# MCU.net
KiCad netlist of a schematic drawn in Altium Designer
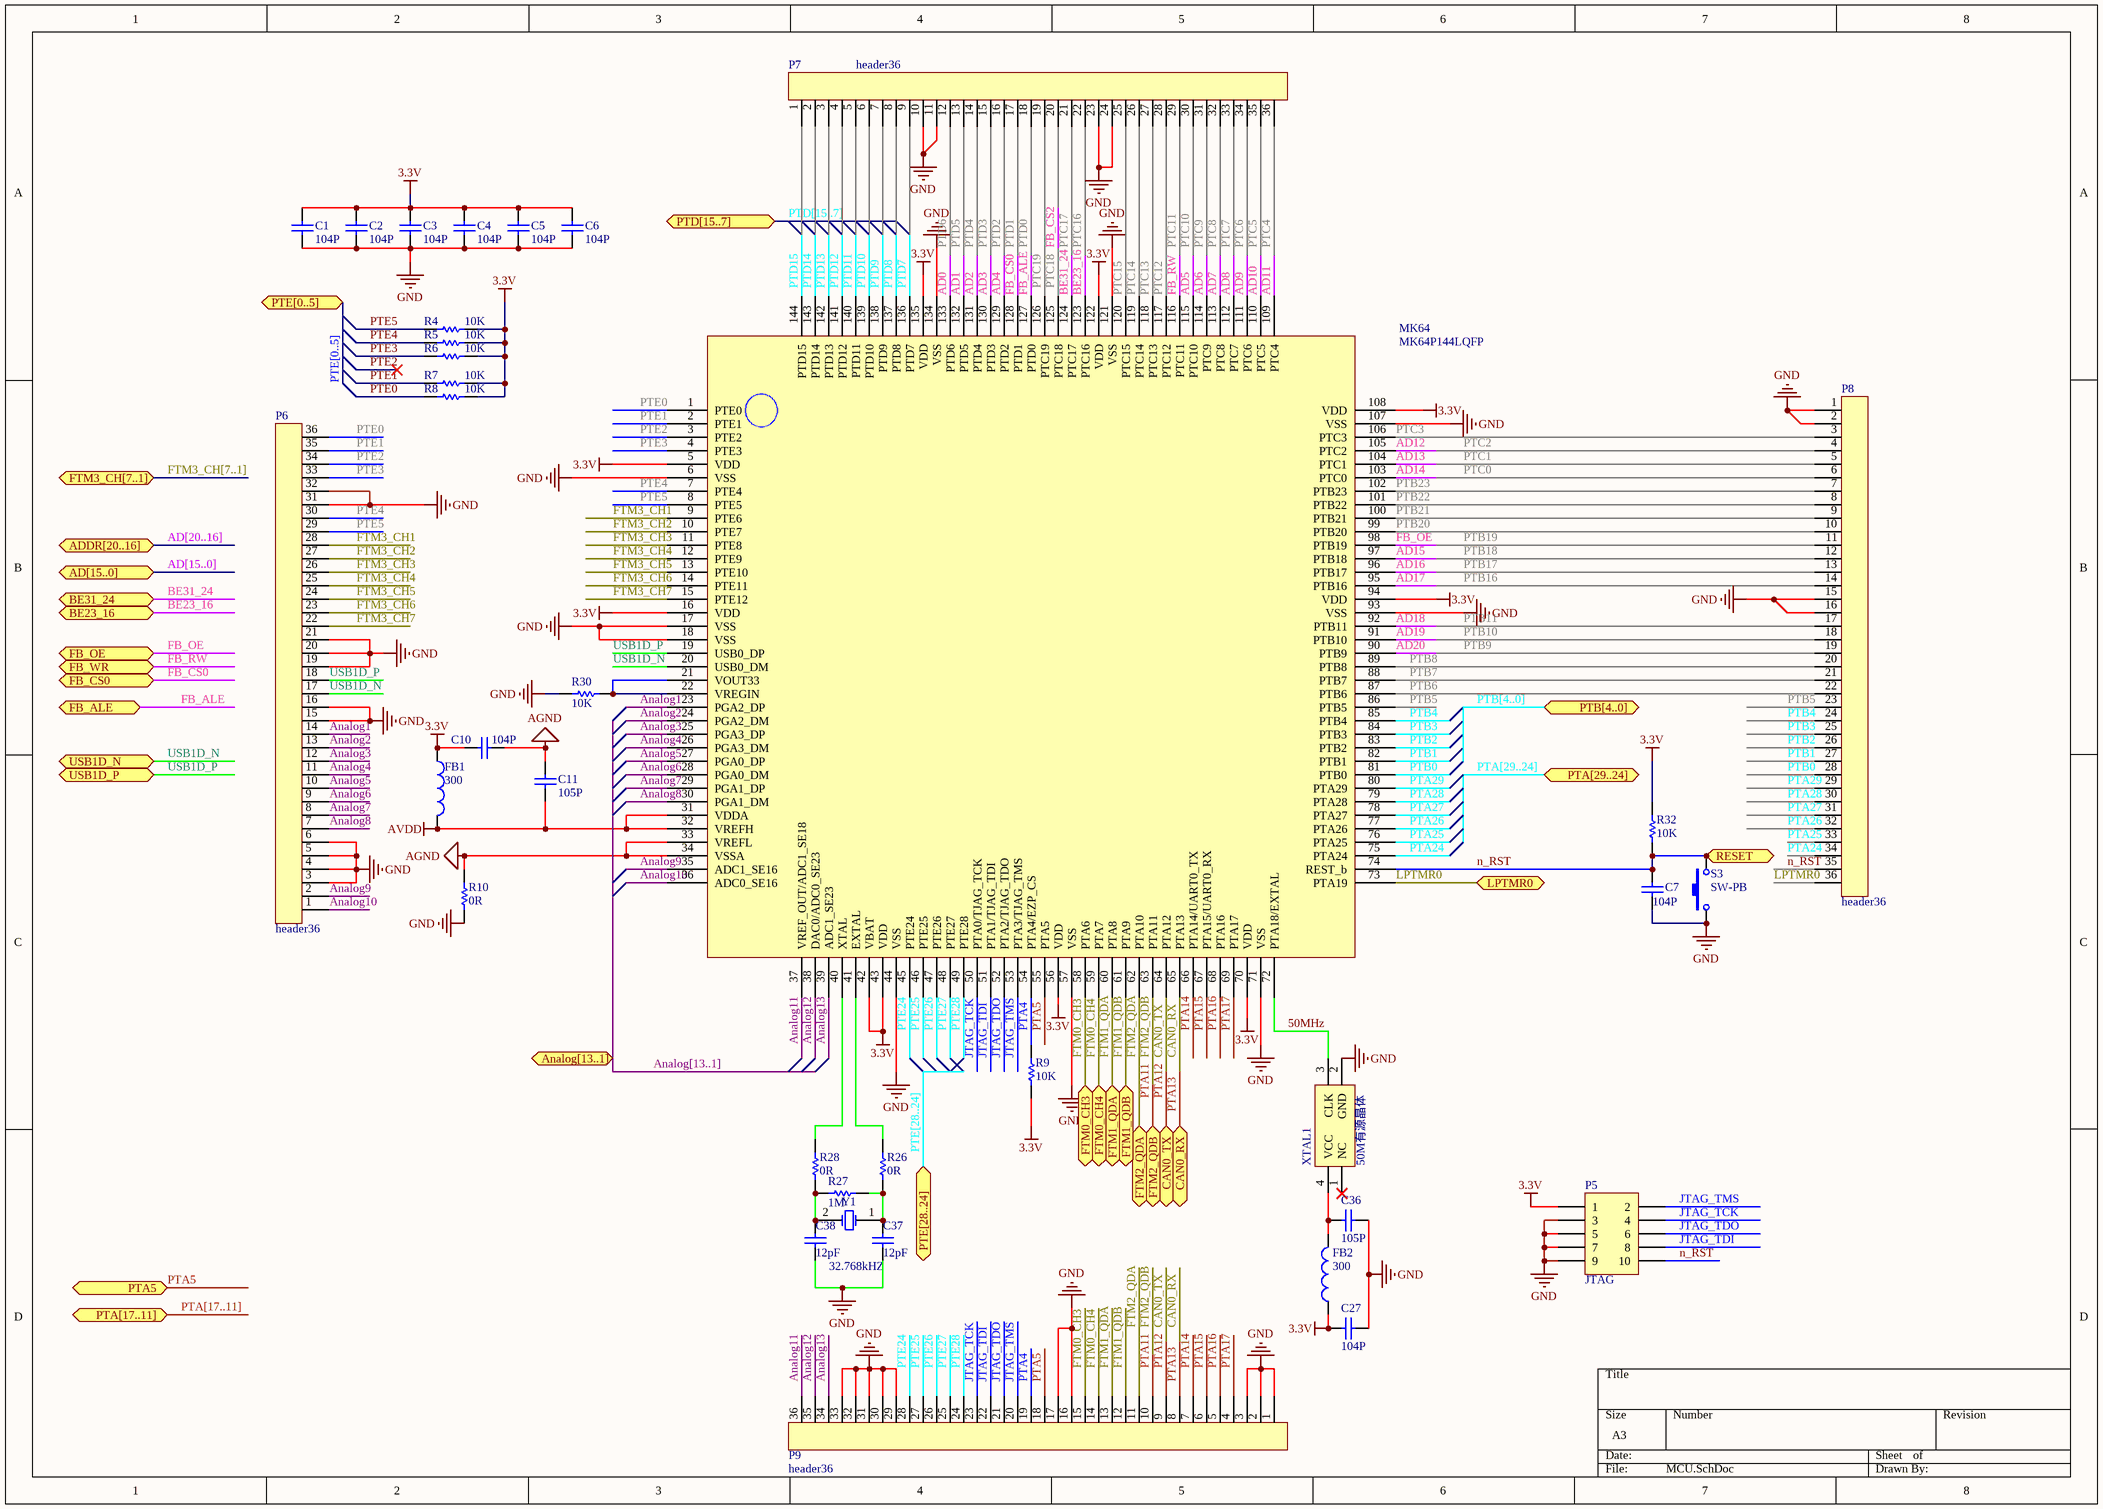
[diagram p0: MCU.SchDoc]

(export (version "E")
  (design (tool "Eeschema 10.0.6"))
  (components
    (comp (ref "C1")
      (value "104P")
      (footprint "1608[0603]")
      (description "贴片电容")
      (fields (field (name "Comment") "Cap") (field (name "PUBLISHER") "Altium Limited"))
      (libsource (lib "Sparks") (part "Cap"))
    )
    (comp (ref "C2")
      (value "104P")
      (footprint "1608[0603]")
      (description "贴片电容")
      (fields (field (name "Comment") "Cap") (field (name "PUBLISHER") "Altium Limited"))
      (libsource (lib "Sparks") (part "Cap"))
    )
    (comp (ref "C3")
      (value "104P")
      (footprint "1608[0603]")
      (description "贴片电容")
      (fields (field (name "Comment") "Cap") (field (name "PUBLISHER") "Altium Limited"))
      (libsource (lib "Sparks") (part "Cap"))
    )
    (comp (ref "C4")
      (value "104P")
      (footprint "1608[0603]")
      (description "贴片电容")
      (fields (field (name "Comment") "Cap") (field (name "PUBLISHER") "Altium Limited"))
      (libsource (lib "Sparks") (part "Cap"))
    )
    (comp (ref "C5")
      (value "104P")
      (footprint "1608[0603]")
      (description "贴片电容")
      (fields (field (name "Comment") "Cap") (field (name "PUBLISHER") "Altium Limited"))
      (libsource (lib "Sparks") (part "Cap"))
    )
    (comp (ref "C6")
      (value "104P")
      (footprint "1608[0603]")
      (description "贴片电容")
      (fields (field (name "Comment") "Cap") (field (name "PUBLISHER") "Altium Limited"))
      (libsource (lib "Sparks") (part "Cap"))
    )
    (comp (ref "C7")
      (value "104P")
      (footprint "1608[0603]")
      (description "贴片电容")
      (fields (field (name "Comment") "Cap") (field (name "PUBLISHER") "Altium Limited"))
      (libsource (lib "Sparks") (part "Cap"))
    )
    (comp (ref "C10")
      (value "104P")
      (footprint "1608[0603]")
      (description "贴片电容")
      (fields (field (name "Comment") "Cap") (field (name "PUBLISHER") "Altium Limited"))
      (libsource (lib "Sparks") (part "Cap"))
    )
    (comp (ref "C11")
      (value "105P")
      (footprint "1608[0603]")
      (description "贴片电容")
      (fields (field (name "Comment") "Cap") (field (name "PUBLISHER") "Altium Limited"))
      (libsource (lib "Sparks") (part "Cap"))
    )
    (comp (ref "C27")
      (value "104P")
      (footprint "1608[0603]")
      (description "贴片电容")
      (fields (field (name "Comment") "Cap") (field (name "PUBLISHER") "Altium Limited"))
      (libsource (lib "Sparks") (part "Cap"))
    )
    (comp (ref "C36")
      (value "105P")
      (footprint "1608[0603]")
      (description "贴片电容")
      (fields (field (name "Comment") "Cap") (field (name "PUBLISHER") "Altium Limited"))
      (libsource (lib "Sparks") (part "Cap"))
    )
    (comp (ref "C37")
      (value "12pF")
      (footprint "1608[0603]")
      (description "贴片电容")
      (fields (field (name "Comment") "Cap") (field (name "PUBLISHER") "Altium Limited"))
      (libsource (lib "Sparks") (part "Cap"))
    )
    (comp (ref "C38")
      (value "12pF")
      (footprint "1608[0603]")
      (description "贴片电容")
      (fields (field (name "Comment") "Cap") (field (name "PUBLISHER") "Altium Limited"))
      (libsource (lib "Sparks") (part "Cap"))
    )
    (comp (ref "FB1")
      (value "300")
      (footprint "1608[0603]")
      (description "Inductor")
      (fields (field (name "PUBLISHER") "Altium Limited"))
      (libsource (lib "Miscellaneous Devices") (part "Inductor"))
    )
    (comp (ref "FB2")
      (value "300")
      (footprint "1608[0603]")
      (description "Inductor")
      (fields (field (name "PUBLISHER") "Altium Limited"))
      (libsource (lib "Miscellaneous Devices") (part "Inductor"))
    )
    (comp (ref "MK64")
      (value "MK64P144LQFP")
      (footprint "LQFP-144")
      (libsource (lib "2号库") (part "MK64P144LQFP"))
    )
    (comp (ref "P5")
      (value "JTAG")
      (footprint "MHDR2X5")
      (description "Header, 5-Pin, Dual row")
      (fields (field (name "PUBLISHER") "Altium Limited"))
      (libsource (lib "Sparks") (part "Header 5X2"))
    )
    (comp (ref "P6") (value "header36") (footprint "FFC/SM0.5-2H36") (libsource (lib "") (part "header36_1")))
    (comp (ref "P7") (value "header36") (footprint "FFC/SM0.5-2H36") (libsource (lib "") (part "header36_2")))
    (comp (ref "P8") (value "header36") (footprint "FFC/SM0.5-2H36") (libsource (lib "") (part "header36_3")))
    (comp (ref "P9")
      (value "header36")
      (footprint "FFC/SM0.5-2H36")
      (libsource (lib "2号库") (part "header36"))
    )
    (comp (ref "R4")
      (value "10K")
      (footprint "1608[0603]")
      (description "贴片电阻")
      (fields (field (name "Comment") "Res") (field (name "PUBLISHER") "Altium Limited"))
      (libsource (lib "Sparks") (part "Res"))
    )
    (comp (ref "R5")
      (value "10K")
      (footprint "1608[0603]")
      (description "贴片电阻")
      (fields (field (name "Comment") "Res") (field (name "PUBLISHER") "Altium Limited"))
      (libsource (lib "Sparks") (part "Res"))
    )
    (comp (ref "R6")
      (value "10K")
      (footprint "1608[0603]")
      (description "贴片电阻")
      (fields (field (name "Comment") "Res") (field (name "PUBLISHER") "Altium Limited"))
      (libsource (lib "Sparks") (part "Res"))
    )
    (comp (ref "R7")
      (value "10K")
      (footprint "1608[0603]")
      (description "贴片电阻")
      (fields (field (name "Comment") "Res") (field (name "PUBLISHER") "Altium Limited"))
      (libsource (lib "Sparks") (part "Res"))
    )
    (comp (ref "R8")
      (value "10K")
      (footprint "1608[0603]")
      (description "贴片电阻")
      (fields (field (name "Comment") "Res") (field (name "PUBLISHER") "Altium Limited"))
      (libsource (lib "Sparks") (part "Res"))
    )
    (comp (ref "R9")
      (value "10K")
      (footprint "1608[0603]")
      (description "贴片电阻")
      (fields (field (name "Comment") "Res") (field (name "PUBLISHER") "Altium Limited"))
      (libsource (lib "Sparks") (part "Res"))
    )
    (comp (ref "R10")
      (value "0R")
      (footprint "1608[0603]")
      (description "贴片电阻")
      (fields (field (name "Comment") "Res") (field (name "PUBLISHER") "Altium Limited"))
      (libsource (lib "Sparks") (part "Res"))
    )
    (comp (ref "R26")
      (value "0R")
      (footprint "1608[0603]")
      (description "贴片电阻")
      (fields (field (name "Comment") "Res") (field (name "PUBLISHER") "Altium Limited"))
      (libsource (lib "Sparks") (part "Res"))
    )
    (comp (ref "R27")
      (value "1M")
      (footprint "1608[0603]")
      (description "贴片电阻")
      (fields (field (name "Comment") "Res") (field (name "PUBLISHER") "Altium Limited"))
      (libsource (lib "Sparks") (part "Res"))
    )
    (comp (ref "R28")
      (value "0R")
      (footprint "1608[0603]")
      (description "贴片电阻")
      (fields (field (name "Comment") "Res") (field (name "PUBLISHER") "Altium Limited"))
      (libsource (lib "Sparks") (part "Res"))
    )
    (comp (ref "R30")
      (value "10K")
      (footprint "1608[0603]")
      (description "贴片电阻")
      (fields (field (name "Comment") "Res") (field (name "PUBLISHER") "Altium Limited"))
      (libsource (lib "Sparks") (part "Res"))
    )
    (comp (ref "R32")
      (value "10K")
      (footprint "1608[0603]")
      (description "贴片电阻")
      (fields (field (name "Comment") "Res") (field (name "PUBLISHER") "Altium Limited"))
      (libsource (lib "Sparks") (part "Res"))
    )
    (comp (ref "S3")
      (value "SW-PB")
      (footprint "key 3*4*2")
      (description "Switch")
      (libsource (lib "K60-V4.0") (part "SW-PB"))
    )
    (comp (ref "XTAL1") (value "50M有源晶体") (footprint "XTAL7_3225") (libsource (lib "Sparks") (part "有源晶体")))
    (comp (ref "Y1")
      (value "32.768kHZ")
      (footprint "3215")
      (description "晶体振荡器")
      (fields (field (name "PUBLISHER") "Altium Limited"))
      (libsource (lib "Sparks") (part "XTAL"))
    )
  )
  (nets
    (net (code "1") (name "/50MHz") (class "Default")
      (node (ref "MK64") (pin "72") (pinfunction "PTA18/EXTAL_72") (pintype "passive"))
      (node (ref "XTAL1") (pin "3") (pinfunction "CLK_3") (pintype "passive"))
    )
    (net (code "2") (name "/AD0") (class "Default")
      (node (ref "MK64") (pin "133") (pinfunction "PTD6_133") (pintype "passive"))
      (node (ref "P7") (pin "12") (pinfunction "12_12") (pintype "passive"))
    )
    (net (code "3") (name "/AD1") (class "Default")
      (node (ref "MK64") (pin "132") (pinfunction "PTD5_132") (pintype "passive"))
      (node (ref "P7") (pin "13") (pinfunction "13_13") (pintype "passive"))
    )
    (net (code "4") (name "/AD2") (class "Default")
      (node (ref "MK64") (pin "131") (pinfunction "PTD4_131") (pintype "passive"))
      (node (ref "P7") (pin "14") (pinfunction "14_14") (pintype "passive"))
    )
    (net (code "5") (name "/AD3") (class "Default")
      (node (ref "MK64") (pin "130") (pinfunction "PTD3_130") (pintype "passive"))
      (node (ref "P7") (pin "15") (pinfunction "15_15") (pintype "passive"))
    )
    (net (code "6") (name "/AD4") (class "Default")
      (node (ref "MK64") (pin "129") (pinfunction "PTD2_129") (pintype "passive"))
      (node (ref "P7") (pin "16") (pinfunction "16_16") (pintype "passive"))
    )
    (net (code "7") (name "/AD5") (class "Default")
      (node (ref "MK64") (pin "115") (pinfunction "PTC10_115") (pintype "passive"))
      (node (ref "P7") (pin "30") (pinfunction "30_30") (pintype "passive"))
    )
    (net (code "8") (name "/AD6") (class "Default")
      (node (ref "MK64") (pin "114") (pinfunction "PTC9_114") (pintype "passive"))
      (node (ref "P7") (pin "31") (pinfunction "31_31") (pintype "passive"))
    )
    (net (code "9") (name "/AD7") (class "Default")
      (node (ref "MK64") (pin "113") (pinfunction "PTC8_113") (pintype "passive"))
      (node (ref "P7") (pin "32") (pinfunction "32_32") (pintype "passive"))
    )
    (net (code "10") (name "/AD8") (class "Default")
      (node (ref "MK64") (pin "112") (pinfunction "PTC7_112") (pintype "passive"))
      (node (ref "P7") (pin "33") (pinfunction "33_33") (pintype "passive"))
    )
    (net (code "11") (name "/AD9") (class "Default")
      (node (ref "MK64") (pin "111") (pinfunction "PTC6_111") (pintype "passive"))
      (node (ref "P7") (pin "34") (pinfunction "34_34") (pintype "passive"))
    )
    (net (code "12") (name "/AD10") (class "Default")
      (node (ref "MK64") (pin "110") (pinfunction "PTC5_110") (pintype "passive"))
      (node (ref "P7") (pin "35") (pinfunction "35_35") (pintype "passive"))
    )
    (net (code "13") (name "/AD11") (class "Default")
      (node (ref "MK64") (pin "109") (pinfunction "PTC4_109") (pintype "passive"))
      (node (ref "P7") (pin "36") (pinfunction "36_36") (pintype "passive"))
    )
    (net (code "14") (name "/AD12") (class "Default")
      (node (ref "MK64") (pin "105") (pinfunction "PTC2_105") (pintype "passive"))
      (node (ref "P8") (pin "4") (pinfunction "4_4") (pintype "passive"))
    )
    (net (code "15") (name "/AD13") (class "Default")
      (node (ref "MK64") (pin "104") (pinfunction "PTC1_104") (pintype "passive"))
      (node (ref "P8") (pin "5") (pinfunction "5_5") (pintype "passive"))
    )
    (net (code "16") (name "/AD14") (class "Default")
      (node (ref "MK64") (pin "103") (pinfunction "PTC0_103") (pintype "passive"))
      (node (ref "P8") (pin "6") (pinfunction "6_6") (pintype "passive"))
    )
    (net (code "17") (name "/AD15") (class "Default")
      (node (ref "MK64") (pin "97") (pinfunction "PTB18_97") (pintype "passive"))
      (node (ref "P8") (pin "12") (pinfunction "12_12") (pintype "passive"))
    )
    (net (code "18") (name "/AD16") (class "Default")
      (node (ref "MK64") (pin "96") (pinfunction "PTB17_96") (pintype "passive"))
      (node (ref "P8") (pin "13") (pinfunction "13_13") (pintype "passive"))
    )
    (net (code "19") (name "/AD17") (class "Default")
      (node (ref "MK64") (pin "95") (pinfunction "PTB16_95") (pintype "passive"))
      (node (ref "P8") (pin "14") (pinfunction "14_14") (pintype "passive"))
    )
    (net (code "20") (name "/AD18") (class "Default")
      (node (ref "MK64") (pin "92") (pinfunction "PTB11_92") (pintype "passive"))
      (node (ref "P8") (pin "17") (pinfunction "17_17") (pintype "passive"))
    )
    (net (code "21") (name "/AD19") (class "Default")
      (node (ref "MK64") (pin "91") (pinfunction "PTB10_91") (pintype "passive"))
      (node (ref "P8") (pin "18") (pinfunction "18_18") (pintype "passive"))
    )
    (net (code "22") (name "/AD20") (class "Default")
      (node (ref "MK64") (pin "90") (pinfunction "PTB9_90") (pintype "passive"))
      (node (ref "P8") (pin "19") (pinfunction "19_19") (pintype "passive"))
    )
    (net (code "25") (name "/Analog1") (class "Default")
      (node (ref "MK64") (pin "23") (pinfunction "PGA2_DP_23") (pintype "passive"))
      (node (ref "P6") (pin "14") (pinfunction "14_14") (pintype "passive"))
    )
    (net (code "26") (name "/Analog2") (class "Default")
      (node (ref "MK64") (pin "24") (pinfunction "PGA2_DM_24") (pintype "passive"))
      (node (ref "P6") (pin "13") (pinfunction "13_13") (pintype "passive"))
    )
    (net (code "27") (name "/Analog3") (class "Default")
      (node (ref "MK64") (pin "25") (pinfunction "PGA3_DP_25") (pintype "passive"))
      (node (ref "P6") (pin "12") (pinfunction "12_12") (pintype "passive"))
    )
    (net (code "28") (name "/Analog4") (class "Default")
      (node (ref "MK64") (pin "26") (pinfunction "PGA3_DM_26") (pintype "passive"))
      (node (ref "P6") (pin "11") (pinfunction "11_11") (pintype "passive"))
    )
    (net (code "29") (name "/Analog5") (class "Default")
      (node (ref "MK64") (pin "27") (pinfunction "PGA0_DP_27") (pintype "passive"))
      (node (ref "P6") (pin "10") (pinfunction "10_10") (pintype "passive"))
    )
    (net (code "30") (name "/Analog6") (class "Default")
      (node (ref "MK64") (pin "28") (pinfunction "PGA0_DM_28") (pintype "passive"))
      (node (ref "P6") (pin "9") (pinfunction "9_9") (pintype "passive"))
    )
    (net (code "31") (name "/Analog7") (class "Default")
      (node (ref "MK64") (pin "29") (pinfunction "PGA1_DP_29") (pintype "passive"))
      (node (ref "P6") (pin "8") (pinfunction "8_8") (pintype "passive"))
    )
    (net (code "32") (name "/Analog8") (class "Default")
      (node (ref "MK64") (pin "30") (pinfunction "PGA1_DM_30") (pintype "passive"))
      (node (ref "P6") (pin "7") (pinfunction "7_7") (pintype "passive"))
    )
    (net (code "33") (name "/Analog9") (class "Default")
      (node (ref "MK64") (pin "35") (pinfunction "ADC1_SE16_35") (pintype "passive"))
      (node (ref "P6") (pin "2") (pinfunction "2_2") (pintype "passive"))
    )
    (net (code "34") (name "/Analog10") (class "Default")
      (node (ref "MK64") (pin "36") (pinfunction "ADC0_SE16_36") (pintype "passive"))
      (node (ref "P6") (pin "1") (pinfunction "1_1") (pintype "passive"))
    )
    (net (code "35") (name "/Analog11") (class "Default")
      (node (ref "MK64") (pin "37") (pinfunction "VREF_OUT/ADC1_SE18_37") (pintype "passive"))
      (node (ref "P9") (pin "36") (pinfunction "36_36") (pintype "passive"))
    )
    (net (code "36") (name "/Analog12") (class "Default")
      (node (ref "MK64") (pin "38") (pinfunction "DAC0/ADC0_SE23_38") (pintype "passive"))
      (node (ref "P9") (pin "35") (pinfunction "35_35") (pintype "passive"))
    )
    (net (code "37") (name "/Analog13") (class "Default")
      (node (ref "MK64") (pin "39") (pinfunction "ADC1_SE23_39") (pintype "passive"))
      (node (ref "P9") (pin "34") (pinfunction "34_34") (pintype "passive"))
    )
    (net (code "39") (name "/BE23_16") (class "Default")
      (node (ref "MK64") (pin "123") (pinfunction "PTC16_123") (pintype "passive"))
      (node (ref "P7") (pin "22") (pinfunction "22_22") (pintype "passive"))
    )
    (net (code "40") (name "/BE31_24") (class "Default")
      (node (ref "MK64") (pin "124") (pinfunction "PTC17_124") (pintype "passive"))
      (node (ref "P7") (pin "21") (pinfunction "21_21") (pintype "passive"))
    )
    (net (code "41") (name "/FB_ALE") (class "Default")
      (node (ref "MK64") (pin "127") (pinfunction "PTD0_127") (pintype "passive"))
      (node (ref "P7") (pin "18") (pinfunction "18_18") (pintype "passive"))
    )
    (net (code "42") (name "/FB_CS0") (class "Default")
      (node (ref "MK64") (pin "128") (pinfunction "PTD1_128") (pintype "passive"))
      (node (ref "P7") (pin "17") (pinfunction "17_17") (pintype "passive"))
    )
    (net (code "43") (name "/FB_CS2") (class "Default")
      (node (ref "MK64") (pin "125") (pinfunction "PTC18_125") (pintype "passive"))
      (node (ref "P7") (pin "20") (pinfunction "20_20") (pintype "passive"))
    )
    (net (code "44") (name "/FB_OE") (class "Default")
      (node (ref "MK64") (pin "98") (pinfunction "PTB19_98") (pintype "passive"))
      (node (ref "P8") (pin "11") (pinfunction "11_11") (pintype "passive"))
    )
    (net (code "45") (name "/FB_RW") (class "Default")
      (node (ref "MK64") (pin "116") (pinfunction "PTC11_116") (pintype "passive"))
      (node (ref "P7") (pin "29") (pinfunction "29_29") (pintype "passive"))
    )
    (net (code "46") (name "/FTM0_CH3") (class "Default")
      (node (ref "MK64") (pin "58") (pinfunction "PTA6_58") (pintype "passive"))
      (node (ref "P9") (pin "15") (pinfunction "15_15") (pintype "passive"))
    )
    (net (code "47") (name "/FTM0_CH4") (class "Default")
      (node (ref "MK64") (pin "59") (pinfunction "PTA7_59") (pintype "passive"))
      (node (ref "P9") (pin "14") (pinfunction "14_14") (pintype "passive"))
    )
    (net (code "48") (name "/FTM1_QDA") (class "Default")
      (node (ref "MK64") (pin "60") (pinfunction "PTA8_60") (pintype "passive"))
      (node (ref "P9") (pin "13") (pinfunction "13_13") (pintype "passive"))
    )
    (net (code "49") (name "/FTM1_QDB") (class "Default")
      (node (ref "MK64") (pin "61") (pinfunction "PTA9_61") (pintype "passive"))
      (node (ref "P9") (pin "12") (pinfunction "12_12") (pintype "passive"))
    )
    (net (code "50") (name "/FTM2_QDA") (class "Default")
      (node (ref "MK64") (pin "62") (pinfunction "PTA10_62") (pintype "passive"))
      (node (ref "P9") (pin "11") (pinfunction "11_11") (pintype "passive"))
    )
    (net (code "51") (name "/FTM3_CH1") (class "Default")
      (node (ref "MK64") (pin "9") (pinfunction "PTE6_9") (pintype "passive"))
      (node (ref "P6") (pin "28") (pinfunction "28_28") (pintype "passive"))
    )
    (net (code "52") (name "/FTM3_CH2") (class "Default")
      (node (ref "MK64") (pin "10") (pinfunction "PTE7_10") (pintype "passive"))
      (node (ref "P6") (pin "27") (pinfunction "27_27") (pintype "passive"))
    )
    (net (code "53") (name "/FTM3_CH3") (class "Default")
      (node (ref "MK64") (pin "11") (pinfunction "PTE8_11") (pintype "passive"))
      (node (ref "P6") (pin "26") (pinfunction "26_26") (pintype "passive"))
    )
    (net (code "54") (name "/FTM3_CH4") (class "Default")
      (node (ref "MK64") (pin "12") (pinfunction "PTE9_12") (pintype "passive"))
      (node (ref "P6") (pin "25") (pinfunction "25_25") (pintype "passive"))
    )
    (net (code "55") (name "/FTM3_CH5") (class "Default")
      (node (ref "MK64") (pin "13") (pinfunction "PTE10_13") (pintype "passive"))
      (node (ref "P6") (pin "24") (pinfunction "24_24") (pintype "passive"))
    )
    (net (code "56") (name "/FTM3_CH6") (class "Default")
      (node (ref "MK64") (pin "14") (pinfunction "PTE11_14") (pintype "passive"))
      (node (ref "P6") (pin "23") (pinfunction "23_23") (pintype "passive"))
    )
    (net (code "57") (name "/FTM3_CH7") (class "Default")
      (node (ref "MK64") (pin "15") (pinfunction "PTE12_15") (pintype "passive"))
      (node (ref "P6") (pin "22") (pinfunction "22_22") (pintype "passive"))
    )
    (net (code "59") (name "/JTAG_TCK") (class "Default")
      (node (ref "MK64") (pin "50") (pinfunction "PTA0/TJAG_TCK_50") (pintype "passive"))
      (node (ref "P5") (pin "4") (pinfunction "4_4") (pintype "passive"))
      (node (ref "P9") (pin "23") (pinfunction "23_23") (pintype "passive"))
    )
    (net (code "60") (name "/JTAG_TDI") (class "Default")
      (node (ref "MK64") (pin "51") (pinfunction "PTA1/TJAG_TDI_51") (pintype "passive"))
      (node (ref "P5") (pin "8") (pinfunction "8_8") (pintype "passive"))
      (node (ref "P9") (pin "22") (pinfunction "22_22") (pintype "passive"))
    )
    (net (code "61") (name "/JTAG_TDO") (class "Default")
      (node (ref "MK64") (pin "52") (pinfunction "PTA2/TJAG_TDO_52") (pintype "passive"))
      (node (ref "P5") (pin "6") (pinfunction "6_6") (pintype "passive"))
      (node (ref "P9") (pin "21") (pinfunction "21_21") (pintype "passive"))
    )
    (net (code "62") (name "/JTAG_TMS") (class "Default")
      (node (ref "MK64") (pin "53") (pinfunction "PTA3/TJAG_TMS_53") (pintype "passive"))
      (node (ref "P5") (pin "2") (pinfunction "2_2") (pintype "passive"))
      (node (ref "P9") (pin "20") (pinfunction "20_20") (pintype "passive"))
    )
    (net (code "63") (name "/LPTMR0") (class "Default")
      (node (ref "MK64") (pin "73") (pinfunction "PTA19_73") (pintype "passive"))
      (node (ref "P8") (pin "36") (pinfunction "36_36") (pintype "passive"))
    )
    (net (code "64") (name "/PTA4") (class "Default")
      (node (ref "MK64") (pin "54") (pinfunction "PTA4/EZP_CS_54") (pintype "passive"))
      (node (ref "P9") (pin "19") (pinfunction "19_19") (pintype "passive"))
      (node (ref "R9") (pin "2") (pinfunction "2_2") (pintype "passive"))
    )
    (net (code "65") (name "/PTA5") (class "Default")
      (node (ref "MK64") (pin "55") (pinfunction "PTA5_55") (pintype "passive"))
      (node (ref "P9") (pin "18") (pinfunction "18_18") (pintype "passive"))
    )
    (net (code "66") (name "/PTA11") (class "Default")
      (node (ref "MK64") (pin "63") (pinfunction "PTA11_63") (pintype "passive"))
      (node (ref "P9") (pin "10") (pinfunction "10_10") (pintype "passive"))
    )
    (net (code "67") (name "/PTA12") (class "Default")
      (node (ref "MK64") (pin "64") (pinfunction "PTA12_64") (pintype "passive"))
      (node (ref "P9") (pin "9") (pinfunction "9_9") (pintype "passive"))
    )
    (net (code "68") (name "/PTA13") (class "Default")
      (node (ref "MK64") (pin "65") (pinfunction "PTA13_65") (pintype "passive"))
      (node (ref "P9") (pin "8") (pinfunction "8_8") (pintype "passive"))
    )
    (net (code "69") (name "/PTA14") (class "Default")
      (node (ref "MK64") (pin "66") (pinfunction "PTA14/UART0_TX_66") (pintype "passive"))
      (node (ref "P9") (pin "7") (pinfunction "7_7") (pintype "passive"))
    )
    (net (code "70") (name "/PTA15") (class "Default")
      (node (ref "MK64") (pin "67") (pinfunction "PTA15/UART0_RX_67") (pintype "passive"))
      (node (ref "P9") (pin "6") (pinfunction "6_6") (pintype "passive"))
    )
    (net (code "71") (name "/PTA16") (class "Default")
      (node (ref "MK64") (pin "68") (pinfunction "PTA16_68") (pintype "passive"))
      (node (ref "P9") (pin "5") (pinfunction "5_5") (pintype "passive"))
    )
    (net (code "72") (name "/PTA17") (class "Default")
      (node (ref "MK64") (pin "69") (pinfunction "PTA17_69") (pintype "passive"))
      (node (ref "P9") (pin "4") (pinfunction "4_4") (pintype "passive"))
    )
    (net (code "73") (name "/PTA24") (class "Default")
      (node (ref "MK64") (pin "75") (pinfunction "PTA24_75") (pintype "passive"))
      (node (ref "P8") (pin "34") (pinfunction "34_34") (pintype "passive"))
    )
    (net (code "74") (name "/PTA25") (class "Default")
      (node (ref "MK64") (pin "76") (pinfunction "PTA25_76") (pintype "passive"))
      (node (ref "P8") (pin "33") (pinfunction "33_33") (pintype "passive"))
    )
    (net (code "75") (name "/PTA26") (class "Default")
      (node (ref "MK64") (pin "77") (pinfunction "PTA26_77") (pintype "passive"))
      (node (ref "P8") (pin "32") (pinfunction "32_32") (pintype "passive"))
    )
    (net (code "76") (name "/PTA27") (class "Default")
      (node (ref "MK64") (pin "78") (pinfunction "PTA27_78") (pintype "passive"))
      (node (ref "P8") (pin "31") (pinfunction "31_31") (pintype "passive"))
    )
    (net (code "77") (name "/PTA28") (class "Default")
      (node (ref "MK64") (pin "79") (pinfunction "PTA28_79") (pintype "passive"))
      (node (ref "P8") (pin "30") (pinfunction "30_30") (pintype "passive"))
    )
    (net (code "78") (name "/PTA29") (class "Default")
      (node (ref "MK64") (pin "80") (pinfunction "PTA29_80") (pintype "passive"))
      (node (ref "P8") (pin "29") (pinfunction "29_29") (pintype "passive"))
    )
    (net (code "81") (name "/PTB0") (class "Default")
      (node (ref "MK64") (pin "81") (pinfunction "PTB0_81") (pintype "passive"))
      (node (ref "P8") (pin "28") (pinfunction "28_28") (pintype "passive"))
    )
    (net (code "82") (name "/PTB1") (class "Default")
      (node (ref "MK64") (pin "82") (pinfunction "PTB1_82") (pintype "passive"))
      (node (ref "P8") (pin "27") (pinfunction "27_27") (pintype "passive"))
    )
    (net (code "83") (name "/PTB2") (class "Default")
      (node (ref "MK64") (pin "83") (pinfunction "PTB2_83") (pintype "passive"))
      (node (ref "P8") (pin "26") (pinfunction "26_26") (pintype "passive"))
    )
    (net (code "84") (name "/PTB3") (class "Default")
      (node (ref "MK64") (pin "84") (pinfunction "PTB3_84") (pintype "passive"))
      (node (ref "P8") (pin "25") (pinfunction "25_25") (pintype "passive"))
    )
    (net (code "85") (name "/PTB4") (class "Default")
      (node (ref "MK64") (pin "85") (pinfunction "PTB4_85") (pintype "passive"))
      (node (ref "P8") (pin "24") (pinfunction "24_24") (pintype "passive"))
    )
    (net (code "86") (name "/PTB5") (class "Default")
      (node (ref "MK64") (pin "86") (pinfunction "PTB5_86") (pintype "passive"))
      (node (ref "P8") (pin "23") (pinfunction "23_23") (pintype "passive"))
    )
    (net (code "87") (name "/PTB6") (class "Default")
      (node (ref "MK64") (pin "87") (pinfunction "PTB6_87") (pintype "passive"))
      (node (ref "P8") (pin "22") (pinfunction "22_22") (pintype "passive"))
    )
    (net (code "88") (name "/PTB7") (class "Default")
      (node (ref "MK64") (pin "88") (pinfunction "PTB7_88") (pintype "passive"))
      (node (ref "P8") (pin "21") (pinfunction "21_21") (pintype "passive"))
    )
    (net (code "89") (name "/PTB8") (class "Default")
      (node (ref "MK64") (pin "89") (pinfunction "PTB8_89") (pintype "passive"))
      (node (ref "P8") (pin "20") (pinfunction "20_20") (pintype "passive"))
    )
    (net (code "90") (name "/PTB20") (class "Default")
      (node (ref "MK64") (pin "99") (pinfunction "PTB20_99") (pintype "passive"))
      (node (ref "P8") (pin "10") (pinfunction "10_10") (pintype "passive"))
    )
    (net (code "91") (name "/PTB21") (class "Default")
      (node (ref "MK64") (pin "100") (pinfunction "PTB21_100") (pintype "passive"))
      (node (ref "P8") (pin "9") (pinfunction "9_9") (pintype "passive"))
    )
    (net (code "92") (name "/PTB22") (class "Default")
      (node (ref "MK64") (pin "101") (pinfunction "PTB22_101") (pintype "passive"))
      (node (ref "P8") (pin "8") (pinfunction "8_8") (pintype "passive"))
    )
    (net (code "93") (name "/PTB23") (class "Default")
      (node (ref "MK64") (pin "102") (pinfunction "PTB23_102") (pintype "passive"))
      (node (ref "P8") (pin "7") (pinfunction "7_7") (pintype "passive"))
    )
    (net (code "95") (name "/PTC3") (class "Default")
      (node (ref "MK64") (pin "106") (pinfunction "PTC3_106") (pintype "passive"))
      (node (ref "P8") (pin "3") (pinfunction "3_3") (pintype "passive"))
    )
    (net (code "96") (name "/PTC12") (class "Default")
      (node (ref "MK64") (pin "117") (pinfunction "PTC12_117") (pintype "passive"))
      (node (ref "P7") (pin "28") (pinfunction "28_28") (pintype "passive"))
    )
    (net (code "97") (name "/PTC13") (class "Default")
      (node (ref "MK64") (pin "118") (pinfunction "PTC13_118") (pintype "passive"))
      (node (ref "P7") (pin "27") (pinfunction "27_27") (pintype "passive"))
    )
    (net (code "98") (name "/PTC14") (class "Default")
      (node (ref "MK64") (pin "119") (pinfunction "PTC14_119") (pintype "passive"))
      (node (ref "P7") (pin "26") (pinfunction "26_26") (pintype "passive"))
    )
    (net (code "99") (name "/PTC15") (class "Default")
      (node (ref "MK64") (pin "120") (pinfunction "PTC15_120") (pintype "passive"))
      (node (ref "P7") (pin "25") (pinfunction "25_25") (pintype "passive"))
    )
    (net (code "100") (name "/PTC19") (class "Default")
      (node (ref "MK64") (pin "126") (pinfunction "PTC19_126") (pintype "passive"))
      (node (ref "P7") (pin "19") (pinfunction "19_19") (pintype "passive"))
    )
    (net (code "101") (name "/PTD7") (class "Default")
      (node (ref "MK64") (pin "136") (pinfunction "PTD7_136") (pintype "passive"))
      (node (ref "P7") (pin "9") (pinfunction "9_9") (pintype "passive"))
    )
    (net (code "102") (name "/PTD8") (class "Default")
      (node (ref "MK64") (pin "137") (pinfunction "PTD8_137") (pintype "passive"))
      (node (ref "P7") (pin "8") (pinfunction "8_8") (pintype "passive"))
    )
    (net (code "103") (name "/PTD9") (class "Default")
      (node (ref "MK64") (pin "138") (pinfunction "PTD9_138") (pintype "passive"))
      (node (ref "P7") (pin "7") (pinfunction "7_7") (pintype "passive"))
    )
    (net (code "104") (name "/PTD10") (class "Default")
      (node (ref "MK64") (pin "139") (pinfunction "PTD10_139") (pintype "passive"))
      (node (ref "P7") (pin "6") (pinfunction "6_6") (pintype "passive"))
    )
    (net (code "105") (name "/PTD11") (class "Default")
      (node (ref "MK64") (pin "140") (pinfunction "PTD11_140") (pintype "passive"))
      (node (ref "P7") (pin "5") (pinfunction "5_5") (pintype "passive"))
    )
    (net (code "106") (name "/PTD12") (class "Default")
      (node (ref "MK64") (pin "141") (pinfunction "PTD12_141") (pintype "passive"))
      (node (ref "P7") (pin "4") (pinfunction "4_4") (pintype "passive"))
    )
    (net (code "107") (name "/PTD13") (class "Default")
      (node (ref "MK64") (pin "142") (pinfunction "PTD13_142") (pintype "passive"))
      (node (ref "P7") (pin "3") (pinfunction "3_3") (pintype "passive"))
    )
    (net (code "108") (name "/PTD14") (class "Default")
      (node (ref "MK64") (pin "143") (pinfunction "PTD14_143") (pintype "passive"))
      (node (ref "P7") (pin "2") (pinfunction "2_2") (pintype "passive"))
    )
    (net (code "109") (name "/PTD15") (class "Default")
      (node (ref "MK64") (pin "144") (pinfunction "PTD15_144") (pintype "passive"))
      (node (ref "P7") (pin "1") (pinfunction "1_1") (pintype "passive"))
    )
    (net (code "111") (name "/PTE0") (class "Default")
      (node (ref "MK64") (pin "1") (pinfunction "PTE0_1") (pintype "passive"))
      (node (ref "P6") (pin "36") (pinfunction "36_36") (pintype "passive"))
      (node (ref "R8") (pin "2") (pinfunction "2_2") (pintype "passive"))
    )
    (net (code "112") (name "/PTE1") (class "Default")
      (node (ref "MK64") (pin "2") (pinfunction "PTE1_2") (pintype "passive"))
      (node (ref "P6") (pin "35") (pinfunction "35_35") (pintype "passive"))
      (node (ref "R7") (pin "2") (pinfunction "2_2") (pintype "passive"))
    )
    (net (code "113") (name "/PTE2") (class "Default")
      (node (ref "MK64") (pin "3") (pinfunction "PTE2_3") (pintype "passive"))
      (node (ref "P6") (pin "34") (pinfunction "34_34") (pintype "passive"))
    )
    (net (code "114") (name "/PTE3") (class "Default")
      (node (ref "MK64") (pin "4") (pinfunction "PTE3_4") (pintype "passive"))
      (node (ref "P6") (pin "33") (pinfunction "33_33") (pintype "passive"))
      (node (ref "R6") (pin "2") (pinfunction "2_2") (pintype "passive"))
    )
    (net (code "115") (name "/PTE4") (class "Default")
      (node (ref "MK64") (pin "7") (pinfunction "PTE4_7") (pintype "passive"))
      (node (ref "P6") (pin "30") (pinfunction "30_30") (pintype "passive"))
      (node (ref "R5") (pin "2") (pinfunction "2_2") (pintype "passive"))
    )
    (net (code "116") (name "/PTE5") (class "Default")
      (node (ref "MK64") (pin "8") (pinfunction "PTE5_8") (pintype "passive"))
      (node (ref "P6") (pin "29") (pinfunction "29_29") (pintype "passive"))
      (node (ref "R4") (pin "2") (pinfunction "2_2") (pintype "passive"))
    )
    (net (code "117") (name "/PTE24") (class "Default")
      (node (ref "MK64") (pin "45") (pinfunction "PTE24_45") (pintype "passive"))
      (node (ref "P9") (pin "28") (pinfunction "28_28") (pintype "passive"))
    )
    (net (code "118") (name "/PTE25") (class "Default")
      (node (ref "MK64") (pin "46") (pinfunction "PTE25_46") (pintype "passive"))
      (node (ref "P9") (pin "27") (pinfunction "27_27") (pintype "passive"))
    )
    (net (code "119") (name "/PTE26") (class "Default")
      (node (ref "MK64") (pin "47") (pinfunction "PTE26_47") (pintype "passive"))
      (node (ref "P9") (pin "26") (pinfunction "26_26") (pintype "passive"))
    )
    (net (code "120") (name "/PTE27") (class "Default")
      (node (ref "MK64") (pin "48") (pinfunction "PTE27_48") (pintype "passive"))
      (node (ref "P9") (pin "25") (pinfunction "25_25") (pintype "passive"))
    )
    (net (code "121") (name "/PTE28") (class "Default")
      (node (ref "MK64") (pin "49") (pinfunction "PTE28_49") (pintype "passive"))
      (node (ref "P9") (pin "24") (pinfunction "24_24") (pintype "passive"))
    )
    (net (code "124") (name "/USB1D_N") (class "Default")
      (node (ref "MK64") (pin "20") (pinfunction "USB0_DM_20") (pintype "passive"))
      (node (ref "P6") (pin "17") (pinfunction "17_17") (pintype "passive"))
    )
    (net (code "125") (name "/USB1D_P") (class "Default")
      (node (ref "MK64") (pin "19") (pinfunction "USB0_DP_19") (pintype "passive"))
      (node (ref "P6") (pin "18") (pinfunction "18_18") (pintype "passive"))
    )
    (net (code "126") (name "/n_RST") (class "Default")
      (node (ref "C7") (pin "2") (pinfunction "2_2") (pintype "passive"))
      (node (ref "MK64") (pin "74") (pinfunction "REST_b_74") (pintype "passive"))
      (node (ref "P5") (pin "10") (pinfunction "10_10") (pintype "passive"))
      (node (ref "P8") (pin "35") (pinfunction "35_35") (pintype "passive"))
      (node (ref "R32") (pin "2") (pinfunction "2_2") (pintype "passive"))
      (node (ref "S3") (pin "2") (pinfunction "2_2") (pintype "passive"))
    )
    (net (code "127") (name "3.3V") (class "Default")
      (node (ref "C1") (pin "2") (pinfunction "2_2") (pintype "passive"))
      (node (ref "C10") (pin "1") (pinfunction "1_1") (pintype "passive"))
      (node (ref "C2") (pin "2") (pinfunction "2_2") (pintype "passive"))
      (node (ref "C27") (pin "2") (pinfunction "2_2") (pintype "passive"))
      (node (ref "C3") (pin "2") (pinfunction "2_2") (pintype "passive"))
      (node (ref "C4") (pin "2") (pinfunction "2_2") (pintype "passive"))
      (node (ref "C5") (pin "2") (pinfunction "2_2") (pintype "passive"))
      (node (ref "C6") (pin "2") (pinfunction "2_2") (pintype "passive"))
      (node (ref "FB1") (pin "1") (pinfunction "1_1") (pintype "passive"))
      (node (ref "FB2") (pin "1") (pinfunction "1_1") (pintype "passive"))
      (node (ref "MK64") (pin "108") (pinfunction "VDD_108") (pintype "passive"))
      (node (ref "MK64") (pin "122") (pinfunction "VDD_122") (pintype "passive"))
      (node (ref "MK64") (pin "135") (pinfunction "VDD_135") (pintype "passive"))
      (node (ref "MK64") (pin "16") (pinfunction "VDD_16") (pintype "passive"))
      (node (ref "MK64") (pin "42") (pinfunction "VBAT_42") (pintype "passive"))
      (node (ref "MK64") (pin "43") (pinfunction "VDD_43") (pintype "passive"))
      (node (ref "MK64") (pin "5") (pinfunction "VDD_5") (pintype "passive"))
      (node (ref "MK64") (pin "56") (pinfunction "VDD_56") (pintype "passive"))
      (node (ref "MK64") (pin "70") (pinfunction "VDD_70") (pintype "passive"))
      (node (ref "MK64") (pin "94") (pinfunction "VDD_94") (pintype "passive"))
      (node (ref "P5") (pin "1") (pinfunction "1_1") (pintype "passive"))
      (node (ref "R32") (pin "1") (pinfunction "1_1") (pintype "passive"))
      (node (ref "R4") (pin "1") (pinfunction "1_1") (pintype "passive"))
      (node (ref "R5") (pin "1") (pinfunction "1_1") (pintype "passive"))
      (node (ref "R6") (pin "1") (pinfunction "1_1") (pintype "passive"))
      (node (ref "R7") (pin "1") (pinfunction "1_1") (pintype "passive"))
      (node (ref "R8") (pin "1") (pinfunction "1_1") (pintype "passive"))
      (node (ref "R9") (pin "1") (pinfunction "1_1") (pintype "passive"))
    )
    (net (code "128") (name "AGND") (class "Default")
      (node (ref "C10") (pin "2") (pinfunction "2_2") (pintype "passive"))
      (node (ref "C11") (pin "2") (pinfunction "2_2") (pintype "passive"))
      (node (ref "MK64") (pin "33") (pinfunction "VREFL_33") (pintype "passive"))
      (node (ref "MK64") (pin "34") (pinfunction "VSSA_34") (pintype "passive"))
      (node (ref "R10") (pin "2") (pinfunction "2_2") (pintype "passive"))
    )
    (net (code "129") (name "AVDD") (class "Default")
      (node (ref "C11") (pin "1") (pinfunction "1_1") (pintype "passive"))
      (node (ref "FB1") (pin "2") (pinfunction "2_2") (pintype "passive"))
      (node (ref "MK64") (pin "31") (pinfunction "VDDA_31") (pintype "passive"))
      (node (ref "MK64") (pin "32") (pinfunction "VREFH_32") (pintype "passive"))
    )
    (net (code "130") (name "GND") (class "Default")
      (node (ref "C1") (pin "1") (pinfunction "1_1") (pintype "passive"))
      (node (ref "C2") (pin "1") (pinfunction "1_1") (pintype "passive"))
      (node (ref "C27") (pin "1") (pinfunction "1_1") (pintype "passive"))
      (node (ref "C3") (pin "1") (pinfunction "1_1") (pintype "passive"))
      (node (ref "C36") (pin "1") (pinfunction "1_1") (pintype "passive"))
      (node (ref "C37") (pin "1") (pinfunction "1_1") (pintype "passive"))
      (node (ref "C38") (pin "1") (pinfunction "1_1") (pintype "passive"))
      (node (ref "C4") (pin "1") (pinfunction "1_1") (pintype "passive"))
      (node (ref "C5") (pin "1") (pinfunction "1_1") (pintype "passive"))
      (node (ref "C6") (pin "1") (pinfunction "1_1") (pintype "passive"))
      (node (ref "C7") (pin "1") (pinfunction "1_1") (pintype "passive"))
      (node (ref "MK64") (pin "107") (pinfunction "VSS_107") (pintype "passive"))
      (node (ref "MK64") (pin "121") (pinfunction "VSS_121") (pintype "passive"))
      (node (ref "MK64") (pin "134") (pinfunction "VSS_134") (pintype "passive"))
      (node (ref "MK64") (pin "17") (pinfunction "VSS_17") (pintype "passive"))
      (node (ref "MK64") (pin "18") (pinfunction "VSS_18") (pintype "passive"))
      (node (ref "MK64") (pin "44") (pinfunction "VSS_44") (pintype "passive"))
      (node (ref "MK64") (pin "57") (pinfunction "VSS_57") (pintype "passive"))
      (node (ref "MK64") (pin "6") (pinfunction "VSS_6") (pintype "passive"))
      (node (ref "MK64") (pin "71") (pinfunction "VSS_71") (pintype "passive"))
      (node (ref "MK64") (pin "93") (pinfunction "VSS_93") (pintype "passive"))
      (node (ref "P5") (pin "3") (pinfunction "3_3") (pintype "passive"))
      (node (ref "P5") (pin "5") (pinfunction "5_5") (pintype "passive"))
      (node (ref "P5") (pin "7") (pinfunction "7_7") (pintype "passive"))
      (node (ref "P5") (pin "9") (pinfunction "9_9") (pintype "passive"))
      (node (ref "P6") (pin "15") (pinfunction "15_15") (pintype "passive"))
      (node (ref "P6") (pin "16") (pinfunction "16_16") (pintype "passive"))
      (node (ref "P6") (pin "19") (pinfunction "19_19") (pintype "passive"))
      (node (ref "P6") (pin "20") (pinfunction "20_20") (pintype "passive"))
      (node (ref "P6") (pin "21") (pinfunction "21_21") (pintype "passive"))
      (node (ref "P6") (pin "3") (pinfunction "3_3") (pintype "passive"))
      (node (ref "P6") (pin "31") (pinfunction "31_31") (pintype "passive"))
      (node (ref "P6") (pin "32") (pinfunction "32_32") (pintype "passive"))
      (node (ref "P6") (pin "4") (pinfunction "4_4") (pintype "passive"))
      (node (ref "P6") (pin "5") (pinfunction "5_5") (pintype "passive"))
      (node (ref "P6") (pin "6") (pinfunction "6_6") (pintype "passive"))
      (node (ref "P7") (pin "10") (pinfunction "10_10") (pintype "passive"))
      (node (ref "P7") (pin "11") (pinfunction "11_11") (pintype "passive"))
      (node (ref "P7") (pin "23") (pinfunction "23_23") (pintype "passive"))
      (node (ref "P7") (pin "24") (pinfunction "24_24") (pintype "passive"))
      (node (ref "P8") (pin "1") (pinfunction "1_1") (pintype "passive"))
      (node (ref "P8") (pin "15") (pinfunction "15_15") (pintype "passive"))
      (node (ref "P8") (pin "16") (pinfunction "16_16") (pintype "passive"))
      (node (ref "P8") (pin "2") (pinfunction "2_2") (pintype "passive"))
      (node (ref "P9") (pin "1") (pinfunction "1_1") (pintype "passive"))
      (node (ref "P9") (pin "16") (pinfunction "16_16") (pintype "passive"))
      (node (ref "P9") (pin "17") (pinfunction "17_17") (pintype "passive"))
      (node (ref "P9") (pin "2") (pinfunction "2_2") (pintype "passive"))
      (node (ref "P9") (pin "29") (pinfunction "29_29") (pintype "passive"))
      (node (ref "P9") (pin "3") (pinfunction "3_3") (pintype "passive"))
      (node (ref "P9") (pin "30") (pinfunction "30_30") (pintype "passive"))
      (node (ref "P9") (pin "31") (pinfunction "31_31") (pintype "passive"))
      (node (ref "P9") (pin "32") (pinfunction "32_32") (pintype "passive"))
      (node (ref "P9") (pin "33") (pinfunction "33_33") (pintype "passive"))
      (node (ref "R10") (pin "1") (pinfunction "1_1") (pintype "passive"))
      (node (ref "R30") (pin "1") (pinfunction "1_1") (pintype "passive"))
      (node (ref "S3") (pin "1") (pinfunction "1_1") (pintype "passive"))
      (node (ref "XTAL1") (pin "2") (pinfunction "GND_2") (pintype "passive"))
    )
    (net (code "131") (name "Net-(MK64-EXTAL)") (class "Default")
      (node (ref "MK64") (pin "41") (pinfunction "EXTAL_41") (pintype "passive"))
      (node (ref "R26") (pin "2") (pinfunction "2_2") (pintype "passive"))
    )
    (net (code "132") (name "Net-(MK64-VOUT33)") (class "Default")
      (node (ref "MK64") (pin "21") (pinfunction "VOUT33_21") (pintype "passive"))
      (node (ref "MK64") (pin "22") (pinfunction "VREGIN_22") (pintype "passive"))
      (node (ref "R30") (pin "2") (pinfunction "2_2") (pintype "passive"))
    )
    (net (code "133") (name "Net-(MK64-XTAL)") (class "Default")
      (node (ref "MK64") (pin "40") (pinfunction "XTAL_40") (pintype "passive"))
      (node (ref "R28") (pin "2") (pinfunction "2_2") (pintype "passive"))
    )
    (net (code "134") (name "Net-(XTAL1-VCC)") (class "Default")
      (node (ref "C36") (pin "2") (pinfunction "2_2") (pintype "passive"))
      (node (ref "FB2") (pin "2") (pinfunction "2_2") (pintype "passive"))
      (node (ref "XTAL1") (pin "4") (pinfunction "VCC_4") (pintype "passive"))
    )
    (net (code "135") (name "Net-(Y1-OSC1)") (class "Default")
      (node (ref "C37") (pin "2") (pinfunction "2_2") (pintype "passive"))
      (node (ref "R26") (pin "1") (pinfunction "1_1") (pintype "passive"))
      (node (ref "R27") (pin "1") (pinfunction "1_1") (pintype "passive"))
      (node (ref "Y1") (pin "1") (pinfunction "OSC1_1") (pintype "passive"))
    )
    (net (code "136") (name "Net-(Y1-OSC2)") (class "Default")
      (node (ref "C38") (pin "2") (pinfunction "2_2") (pintype "passive"))
      (node (ref "R27") (pin "2") (pinfunction "2_2") (pintype "passive"))
      (node (ref "R28") (pin "1") (pinfunction "1_1") (pintype "passive"))
      (node (ref "Y1") (pin "2") (pinfunction "OSC2_2") (pintype "passive"))
    )
    (net (code "137") (name "unconnected-(XTAL1-NC-Pad1)") (class "Default")
      (node (ref "XTAL1") (pin "1") (pinfunction "NC_1") (pintype "passive+no_connect"))
    )
  )
)
